# dsPIC_I2C.net
KiCad netlist of a schematic drawn in EAGLE
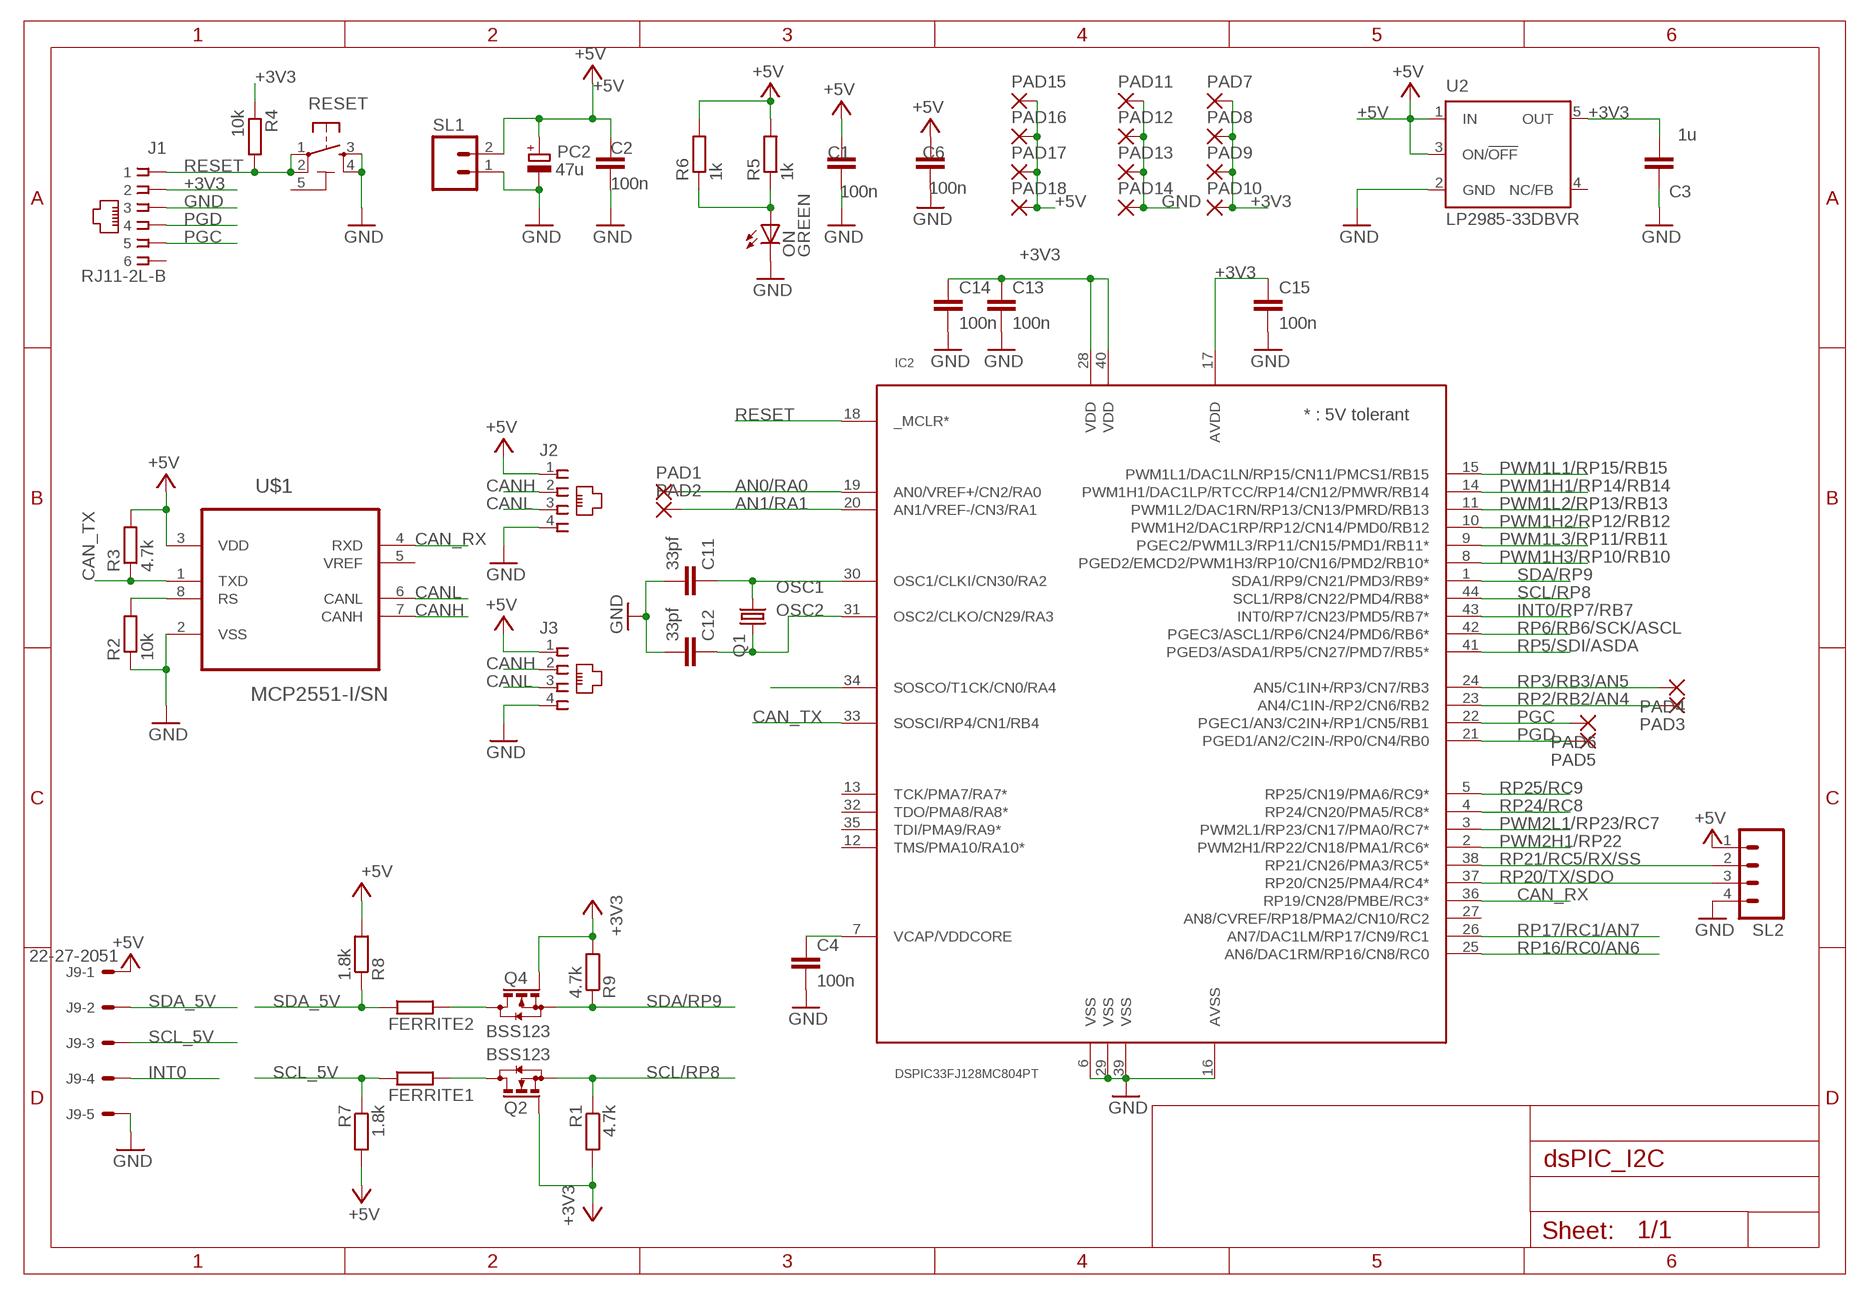
[diagram p0: schematic, sheet 1]

(export (version "E")
  (design (tool "Eeschema 10.0.6"))
  (components
    (comp (ref "C1")
      (value "100n")
      (footprint "eagle-import:C0603-ROUND")
      (libsource (lib "eagle-import") (part "C-EU0603-RND"))
    )
    (comp (ref "C2")
      (value "100n")
      (footprint "eagle-import:C0603-ROUND")
      (libsource (lib "eagle-import") (part "C-EU0603-RND"))
    )
    (comp (ref "C3")
      (value "1u")
      (footprint "eagle-import:C0603-ROUND")
      (libsource (lib "eagle-import") (part "C-EU0603-RND"))
    )
    (comp (ref "C4")
      (value "100n")
      (footprint "eagle-import:C0603K")
      (libsource (lib "eagle-import") (part "SmartPrj_C-EUC0603K"))
    )
    (comp (ref "C6")
      (value "100n")
      (footprint "eagle-import:C0603K")
      (libsource (lib "eagle-import") (part "SmartPrj_C-EUC0603K"))
    )
    (comp (ref "C11")
      (value "33pf")
      (footprint "eagle-import:C0603")
      (libsource (lib "eagle-import") (part "C-EUC0603"))
    )
    (comp (ref "C12")
      (value "33pf")
      (footprint "eagle-import:C0603")
      (libsource (lib "eagle-import") (part "C-EUC0603"))
    )
    (comp (ref "C13")
      (value "100n")
      (footprint "eagle-import:C0603")
      (libsource (lib "eagle-import") (part "C-EUC0603"))
    )
    (comp (ref "C14")
      (value "100n")
      (footprint "eagle-import:C0603")
      (libsource (lib "eagle-import") (part "C-EUC0603"))
    )
    (comp (ref "C15")
      (value "100n")
      (footprint "eagle-import:C0603")
      (libsource (lib "eagle-import") (part "C-EUC0603"))
    )
    (comp (ref "FERRITE1")
      (value "R-EU_M0805")
      (footprint "eagle-import:M0805")
      (libsource (lib "eagle-import") (part "R-EU_M0805"))
    )
    (comp (ref "FERRITE2")
      (value "R-EU_M0805")
      (footprint "eagle-import:M0805")
      (libsource (lib "eagle-import") (part "R-EU_M0805"))
    )
    (comp (ref "IC2")
      (value "DSPIC33FJ128MC804PT")
      (footprint "eagle-import:TQFP44")
      (libsource (lib "eagle-import") (part "DSPIC33F04PTJ128MC8"))
    )
    (comp (ref "J1")
      (value "RJ11-2L-B")
      (footprint "eagle-import:RJ11-NO_SHIELD")
      (fields (field (name "MF") "TYCO ELECTRONICS") (field (name "OC_FARNELL") "1393306"))
      (libsource (lib "eagle-import") (part "RJ11-2L-B"))
    )
    (comp (ref "J2")
      (value "520249-2")
      (footprint "eagle-import:520249-2")
      (libsource (lib "eagle-import") (part "520249-2"))
    )
    (comp (ref "J3")
      (value "520249-2")
      (footprint "eagle-import:520249-2")
      (libsource (lib "eagle-import") (part "520249-2"))
    )
    (comp (ref "J9")
      (value "22-27-2051")
      (footprint "eagle-import:6410-05")
      (libsource (lib "eagle-import") (part "22-?-0527-2051"))
    )
    (comp (ref "ON")
      (value "GREEN")
      (footprint "eagle-import:CHIP-LED0805")
      (libsource (lib "eagle-import") (part "LEDCHIP-LED0805"))
    )
    (comp (ref "PAD1")
      (value "1,6/0,9")
      (footprint "eagle-import:1,6_0,9")
      (libsource (lib "eagle-import") (part "1,6/0,9"))
    )
    (comp (ref "PAD2")
      (value "1,6/0,9")
      (footprint "eagle-import:1,6_0,9")
      (libsource (lib "eagle-import") (part "1,6/0,9"))
    )
    (comp (ref "PAD3")
      (value "1,6/0,9")
      (footprint "eagle-import:1,6_0,9")
      (libsource (lib "eagle-import") (part "1,6/0,9"))
    )
    (comp (ref "PAD4")
      (value "1,6/0,9")
      (footprint "eagle-import:1,6_0,9")
      (libsource (lib "eagle-import") (part "1,6/0,9"))
    )
    (comp (ref "PAD5")
      (value "1,6/0,9")
      (footprint "eagle-import:1,6_0,9")
      (libsource (lib "eagle-import") (part "1,6/0,9"))
    )
    (comp (ref "PAD6")
      (value "1,6/0,9")
      (footprint "eagle-import:1,6_0,9")
      (libsource (lib "eagle-import") (part "1,6/0,9"))
    )
    (comp (ref "PAD7")
      (value "1,6/0,9")
      (footprint "eagle-import:1,6_0,9")
      (libsource (lib "eagle-import") (part "1,6/0,9"))
    )
    (comp (ref "PAD8")
      (value "1,6/0,9")
      (footprint "eagle-import:1,6_0,9")
      (libsource (lib "eagle-import") (part "1,6/0,9"))
    )
    (comp (ref "PAD9")
      (value "1,6/0,9")
      (footprint "eagle-import:1,6_0,9")
      (libsource (lib "eagle-import") (part "1,6/0,9"))
    )
    (comp (ref "PAD10")
      (value "1,6/0,9")
      (footprint "eagle-import:1,6_0,9")
      (libsource (lib "eagle-import") (part "1,6/0,9"))
    )
    (comp (ref "PAD11")
      (value "1,6/0,9")
      (footprint "eagle-import:1,6_0,9")
      (libsource (lib "eagle-import") (part "1,6/0,9"))
    )
    (comp (ref "PAD12")
      (value "1,6/0,9")
      (footprint "eagle-import:1,6_0,9")
      (libsource (lib "eagle-import") (part "1,6/0,9"))
    )
    (comp (ref "PAD13")
      (value "1,6/0,9")
      (footprint "eagle-import:1,6_0,9")
      (libsource (lib "eagle-import") (part "1,6/0,9"))
    )
    (comp (ref "PAD14")
      (value "1,6/0,9")
      (footprint "eagle-import:1,6_0,9")
      (libsource (lib "eagle-import") (part "1,6/0,9"))
    )
    (comp (ref "PAD15")
      (value "1,6/0,9")
      (footprint "eagle-import:1,6_0,9")
      (libsource (lib "eagle-import") (part "1,6/0,9"))
    )
    (comp (ref "PAD16")
      (value "1,6/0,9")
      (footprint "eagle-import:1,6_0,9")
      (libsource (lib "eagle-import") (part "1,6/0,9"))
    )
    (comp (ref "PAD17")
      (value "1,6/0,9")
      (footprint "eagle-import:1,6_0,9")
      (libsource (lib "eagle-import") (part "1,6/0,9"))
    )
    (comp (ref "PAD18")
      (value "1,6/0,9")
      (footprint "eagle-import:1,6_0,9")
      (libsource (lib "eagle-import") (part "1,6/0,9"))
    )
    (comp (ref "PC2")
      (value "47u")
      (footprint "eagle-import:PANASONIC_D")
      (libsource (lib "eagle-import") (part "CPOL-EUD"))
    )
    (comp (ref "Q1")
      (value "CRYSTALSM49")
      (footprint "eagle-import:SM49")
      (fields (field (name "OC_FARNELL") "1842332"))
      (libsource (lib "eagle-import") (part "CRYSTALSM49"))
    )
    (comp (ref "Q2")
      (value "BSS123")
      (footprint "eagle-import:SOT23")
      (libsource (lib "eagle-import") (part "BSS123"))
    )
    (comp (ref "Q4")
      (value "BSS123")
      (footprint "eagle-import:SOT23")
      (libsource (lib "eagle-import") (part "BSS123"))
    )
    (comp (ref "R1")
      (value "4.7k")
      (footprint "eagle-import:R0805")
      (libsource (lib "eagle-import") (part "rcl_R-EU_R0805"))
    )
    (comp (ref "R2")
      (value "10k")
      (footprint "eagle-import:R0805")
      (libsource (lib "eagle-import") (part "R-EU_R0805"))
    )
    (comp (ref "R3")
      (value "4.7k")
      (footprint "eagle-import:R0805")
      (libsource (lib "eagle-import") (part "R-EU_R0805"))
    )
    (comp (ref "R4")
      (value "10k")
      (footprint "eagle-import:R0805")
      (libsource (lib "eagle-import") (part "R-EU_R0805"))
    )
    (comp (ref "R5")
      (value "1k")
      (footprint "eagle-import:R0805")
      (libsource (lib "eagle-import") (part "R-EU_R0805"))
    )
    (comp (ref "R6")
      (value "1k")
      (footprint "eagle-import:R0805")
      (libsource (lib "eagle-import") (part "R-EU_R0805"))
    )
    (comp (ref "R7")
      (value "1.8k")
      (footprint "eagle-import:0204_7")
      (libsource (lib "eagle-import") (part "rcl_R-EU_0204/7"))
    )
    (comp (ref "R8")
      (value "1.8k")
      (footprint "eagle-import:0204_7")
      (libsource (lib "eagle-import") (part "rcl_R-EU_0204/7"))
    )
    (comp (ref "R9")
      (value "4.7k")
      (footprint "eagle-import:R0805")
      (libsource (lib "eagle-import") (part "rcl_R-EU_R0805"))
    )
    (comp (ref "RESET")
      (value "TS42031-160R-TR-7260")
      (footprint "eagle-import:TS42")
      (libsource (lib "eagle-import") (part "TS42"))
    )
    (comp (ref "SL1")
      (value "M02")
      (footprint "eagle-import:02P")
      (libsource (lib "eagle-import") (part "M02"))
    )
    (comp (ref "SL2")
      (value "M04")
      (footprint "eagle-import:04P")
      (libsource (lib "eagle-import") (part "M04"))
    )
    (comp (ref "U$1")
      (value "MCP2551-I/SN")
      (footprint "eagle-import:SOIC127P600X175-8N")
      (libsource (lib "eagle-import") (part "MCP2551-I/SN"))
    )
    (comp (ref "U2")
      (value "LP2985-33DBVR")
      (footprint "eagle-import:SOT23-DBV")
      (libsource (lib "eagle-import") (part "LP2985-XXDBVR33"))
    )
  )
  (nets
    (net (code "1") (name "+3V3") (class "Default")
      (node (ref "C13") (pin "1") (pinfunction "1_1") (pintype "passive"))
      (node (ref "C14") (pin "1") (pinfunction "1_1") (pintype "passive"))
      (node (ref "C15") (pin "1") (pinfunction "1_1") (pintype "passive"))
      (node (ref "C3") (pin "2") (pinfunction "2_2") (pintype "passive"))
      (node (ref "IC2") (pin "17") (pinfunction "AVDD_17") (pintype "power_in"))
      (node (ref "IC2") (pin "28") (pinfunction "VDD_28") (pintype "power_in"))
      (node (ref "IC2") (pin "40") (pinfunction "VDD_40") (pintype "power_in"))
      (node (ref "J1") (pin "2") (pinfunction "2_2") (pintype "passive"))
      (node (ref "PAD10") (pin "1") (pinfunction "P_1") (pintype "passive"))
      (node (ref "PAD7") (pin "1") (pinfunction "P_1") (pintype "passive"))
      (node (ref "PAD8") (pin "1") (pinfunction "P_1") (pintype "passive"))
      (node (ref "PAD9") (pin "1") (pinfunction "P_1") (pintype "passive"))
      (node (ref "Q2") (pin "1") (pinfunction "G_1") (pintype "passive"))
      (node (ref "Q4") (pin "1") (pinfunction "G_1") (pintype "passive"))
      (node (ref "R1") (pin "2") (pinfunction "2_2") (pintype "passive"))
      (node (ref "R4") (pin "1") (pinfunction "1_1") (pintype "passive"))
      (node (ref "R9") (pin "2") (pinfunction "2_2") (pintype "passive"))
      (node (ref "U2") (pin "5") (pinfunction "OUT_5") (pintype "passive"))
    )
    (net (code "2") (name "+5V") (class "Default")
      (node (ref "C1") (pin "2") (pinfunction "2_2") (pintype "passive"))
      (node (ref "C2") (pin "2") (pinfunction "2_2") (pintype "passive"))
      (node (ref "C6") (pin "2") (pinfunction "2_2") (pintype "passive"))
      (node (ref "J2") (pin "1") (pinfunction "1_1") (pintype "passive"))
      (node (ref "J3") (pin "1") (pinfunction "1_1") (pintype "passive"))
      (node (ref "J9") (pin "1") (pinfunction "S_1") (pintype "passive"))
      (node (ref "PAD15") (pin "1") (pinfunction "P_1") (pintype "passive"))
      (node (ref "PAD16") (pin "1") (pinfunction "P_1") (pintype "passive"))
      (node (ref "PAD17") (pin "1") (pinfunction "P_1") (pintype "passive"))
      (node (ref "PAD18") (pin "1") (pinfunction "P_1") (pintype "passive"))
      (node (ref "PC2") (pin "+") (pinfunction "+_+") (pintype "passive"))
      (node (ref "R3") (pin "2") (pinfunction "2_2") (pintype "passive"))
      (node (ref "R5") (pin "2") (pinfunction "2_2") (pintype "passive"))
      (node (ref "R6") (pin "2") (pinfunction "2_2") (pintype "passive"))
      (node (ref "R7") (pin "2") (pinfunction "2_2") (pintype "passive"))
      (node (ref "R8") (pin "2") (pinfunction "2_2") (pintype "passive"))
      (node (ref "SL1") (pin "2") (pinfunction "2_2") (pintype "passive"))
      (node (ref "SL2") (pin "1") (pinfunction "1_1") (pintype "passive"))
      (node (ref "U$1") (pin "3") (pinfunction "VDD_3") (pintype "power_in"))
      (node (ref "U2") (pin "1") (pinfunction "IN_1") (pintype "input"))
      (node (ref "U2") (pin "3") (pinfunction "ON/~{OFF}_3") (pintype "input"))
    )
    (net (code "3") (name "/5-GND") (class "Default")
      (node (ref "RESET") (pin "5") (pinfunction "5-GND_5") (pintype "power_in"))
    )
    (net (code "4") (name "/AN0{slash}RA0") (class "Default")
      (node (ref "IC2") (pin "19") (pinfunction "AN0/VREF+/CN2/RA0_19") (pintype "bidirectional"))
      (node (ref "PAD1") (pin "1") (pinfunction "P_1") (pintype "passive"))
    )
    (net (code "5") (name "/AN1{slash}RA1") (class "Default")
      (node (ref "IC2") (pin "20") (pinfunction "AN1/VREF-/CN3/RA1_20") (pintype "bidirectional"))
      (node (ref "PAD2") (pin "1") (pinfunction "P_1") (pintype "passive"))
    )
    (net (code "6") (name "/CANH") (class "Default")
      (node (ref "J2") (pin "2") (pinfunction "2_2") (pintype "passive"))
      (node (ref "J3") (pin "2") (pinfunction "2_2") (pintype "passive"))
      (node (ref "U$1") (pin "7") (pinfunction "CANH_7") (pintype "bidirectional"))
    )
    (net (code "7") (name "/CANL") (class "Default")
      (node (ref "J2") (pin "3") (pinfunction "3_3") (pintype "passive"))
      (node (ref "J3") (pin "3") (pinfunction "3_3") (pintype "passive"))
      (node (ref "U$1") (pin "6") (pinfunction "CANL_6") (pintype "bidirectional"))
    )
    (net (code "8") (name "/CAN_RX") (class "Default")
      (node (ref "IC2") (pin "36") (pinfunction "RP19/CN28/PMBE/RC3*_36") (pintype "bidirectional"))
      (node (ref "U$1") (pin "4") (pinfunction "RXD_4") (pintype "output"))
    )
    (net (code "9") (name "/CAN_TX") (class "Default")
      (node (ref "IC2") (pin "33") (pinfunction "SOSCI/RP4/CN1/RB4_33") (pintype "bidirectional"))
      (node (ref "R3") (pin "1") (pinfunction "1_1") (pintype "passive"))
      (node (ref "U$1") (pin "1") (pinfunction "TXD_1") (pintype "input"))
    )
    (net (code "10") (name "/INT0") (class "Default")
      (node (ref "J9") (pin "4") (pinfunction "S_4") (pintype "passive"))
    )
    (net (code "11") (name "/INT0{slash}RP7{slash}RB7") (class "Default")
      (node (ref "IC2") (pin "43") (pinfunction "INT0/RP7/CN23/PMD5/RB7*_43") (pintype "bidirectional"))
    )
    (net (code "12") (name "/OSC1") (class "Default")
      (node (ref "C11") (pin "1") (pinfunction "1_1") (pintype "passive"))
      (node (ref "IC2") (pin "30") (pinfunction "OSC1/CLKI/CN30/RA2_30") (pintype "bidirectional"))
      (node (ref "Q1") (pin "1") (pinfunction "1_1") (pintype "passive"))
    )
    (net (code "13") (name "/OSC2") (class "Default")
      (node (ref "C12") (pin "1") (pinfunction "1_1") (pintype "passive"))
      (node (ref "IC2") (pin "31") (pinfunction "OSC2/CLKO/CN29/RA3_31") (pintype "bidirectional"))
      (node (ref "Q1") (pin "2") (pinfunction "2_2") (pintype "passive"))
    )
    (net (code "14") (name "/PGC") (class "Default")
      (node (ref "IC2") (pin "22") (pinfunction "PGEC1/AN3/C2IN+/RP1/CN5/RB1_22") (pintype "bidirectional"))
      (node (ref "J1") (pin "5") (pinfunction "5_5") (pintype "passive"))
      (node (ref "PAD6") (pin "1") (pinfunction "P_1") (pintype "passive"))
    )
    (net (code "15") (name "/PGD") (class "Default")
      (node (ref "IC2") (pin "21") (pinfunction "PGED1/AN2/C2IN-/RP0/CN4/RB0_21") (pintype "bidirectional"))
      (node (ref "J1") (pin "4") (pinfunction "4_4") (pintype "passive"))
      (node (ref "PAD5") (pin "1") (pinfunction "P_1") (pintype "passive"))
    )
    (net (code "16") (name "/PWM1H1{slash}RP14{slash}RB14") (class "Default")
      (node (ref "IC2") (pin "14") (pinfunction "PWM1H1/DAC1LP/RTCC/RP14/CN12/PMWR/RB14_14") (pintype "bidirectional"))
    )
    (net (code "17") (name "/PWM1H2{slash}RP12{slash}RB12") (class "Default")
      (node (ref "IC2") (pin "10") (pinfunction "PWM1H2/DAC1RP/RP12/CN14/PMD0/RB12_10") (pintype "bidirectional"))
    )
    (net (code "18") (name "/PWM1H3{slash}RP10{slash}RB10") (class "Default")
      (node (ref "IC2") (pin "8") (pinfunction "PGED2/EMCD2/PWM1H3/RP10/CN16/PMD2/RB10*_8") (pintype "bidirectional"))
    )
    (net (code "19") (name "/PWM1L1{slash}RP15{slash}RB15") (class "Default")
      (node (ref "IC2") (pin "15") (pinfunction "PWM1L1/DAC1LN/RP15/CN11/PMCS1/RB15_15") (pintype "bidirectional"))
    )
    (net (code "20") (name "/PWM1L2{slash}RP13{slash}RB13") (class "Default")
      (node (ref "IC2") (pin "11") (pinfunction "PWM1L2/DAC1RN/RP13/CN13/PMRD/RB13_11") (pintype "bidirectional"))
    )
    (net (code "21") (name "/PWM1L3{slash}RP11{slash}RB11") (class "Default")
      (node (ref "IC2") (pin "9") (pinfunction "PGEC2/PWM1L3/RP11/CN15/PMD1/RB11*_9") (pintype "bidirectional"))
    )
    (net (code "22") (name "/PWM2H1{slash}RP22") (class "Default")
      (node (ref "IC2") (pin "2") (pinfunction "PWM2H1/RP22/CN18/PMA1/RC6*_2") (pintype "bidirectional"))
    )
    (net (code "23") (name "/PWM2L1{slash}RP23{slash}RC7") (class "Default")
      (node (ref "IC2") (pin "3") (pinfunction "PWM2L1/RP23/CN17/PMA0/RC7*_3") (pintype "bidirectional"))
    )
    (net (code "24") (name "/RESET") (class "Default")
      (node (ref "IC2") (pin "18") (pinfunction "_MCLR*_18") (pintype "input"))
      (node (ref "J1") (pin "1") (pinfunction "1_1") (pintype "passive"))
      (node (ref "R4") (pin "2") (pinfunction "2_2") (pintype "passive"))
      (node (ref "RESET") (pin "1") (pinfunction "1_1") (pintype "passive"))
      (node (ref "RESET") (pin "2") (pinfunction "2_2") (pintype "passive"))
    )
    (net (code "25") (name "/RP2{slash}RB2{slash}AN4") (class "Default")
      (node (ref "IC2") (pin "23") (pinfunction "AN4/C1IN-/RP2/CN6/RB2_23") (pintype "bidirectional"))
      (node (ref "PAD3") (pin "1") (pinfunction "P_1") (pintype "passive"))
    )
    (net (code "26") (name "/RP3{slash}RB3{slash}AN5") (class "Default")
      (node (ref "IC2") (pin "24") (pinfunction "AN5/C1IN+/RP3/CN7/RB3_24") (pintype "bidirectional"))
      (node (ref "PAD4") (pin "1") (pinfunction "P_1") (pintype "passive"))
    )
    (net (code "27") (name "/RP5{slash}SDI{slash}ASDA") (class "Default")
      (node (ref "IC2") (pin "41") (pinfunction "PGED3/ASDA1/RP5/CN27/PMD7/RB5*_41") (pintype "bidirectional"))
    )
    (net (code "28") (name "/RP6{slash}RB6{slash}SCK{slash}ASCL") (class "Default")
      (node (ref "IC2") (pin "42") (pinfunction "PGEC3/ASCL1/RP6/CN24/PMD6/RB6*_42") (pintype "bidirectional"))
    )
    (net (code "29") (name "/RP16{slash}RC0{slash}AN6") (class "Default")
      (node (ref "IC2") (pin "25") (pinfunction "AN6/DAC1RM/RP16/CN8/RC0_25") (pintype "bidirectional"))
    )
    (net (code "30") (name "/RP17{slash}RC1{slash}AN7") (class "Default")
      (node (ref "IC2") (pin "26") (pinfunction "AN7/DAC1LM/RP17/CN9/RC1_26") (pintype "bidirectional"))
    )
    (net (code "31") (name "/RP20{slash}TX{slash}SDO") (class "Default")
      (node (ref "IC2") (pin "37") (pinfunction "RP20/CN25/PMA4/RC4*_37") (pintype "bidirectional"))
      (node (ref "SL2") (pin "3") (pinfunction "3_3") (pintype "passive"))
    )
    (net (code "32") (name "/RP21{slash}RC5{slash}RX{slash}SS") (class "Default")
      (node (ref "IC2") (pin "38") (pinfunction "RP21/CN26/PMA3/RC5*_38") (pintype "bidirectional"))
      (node (ref "SL2") (pin "2") (pinfunction "2_2") (pintype "passive"))
    )
    (net (code "33") (name "/RP24{slash}RC8") (class "Default")
      (node (ref "IC2") (pin "4") (pinfunction "RP24/CN20/PMA5/RC8*_4") (pintype "bidirectional"))
    )
    (net (code "34") (name "/RP25{slash}RC9") (class "Default")
      (node (ref "IC2") (pin "5") (pinfunction "RP25/CN19/PMA6/RC9*_5") (pintype "bidirectional"))
    )
    (net (code "35") (name "/SCL_5V") (class "Default")
      (node (ref "FERRITE1") (pin "1") (pinfunction "1_1") (pintype "passive"))
      (node (ref "J9") (pin "3") (pinfunction "S_3") (pintype "passive"))
      (node (ref "R7") (pin "1") (pinfunction "1_1") (pintype "passive"))
    )
    (net (code "36") (name "/SCL{slash}RP8") (class "Default")
      (node (ref "IC2") (pin "44") (pinfunction "SCL1/RP8/CN22/PMD4/RB8*_44") (pintype "bidirectional"))
      (node (ref "Q2") (pin "2") (pinfunction "S_2") (pintype "passive"))
      (node (ref "R1") (pin "1") (pinfunction "1_1") (pintype "passive"))
    )
    (net (code "37") (name "/SDA_5V") (class "Default")
      (node (ref "FERRITE2") (pin "1") (pinfunction "1_1") (pintype "passive"))
      (node (ref "J9") (pin "2") (pinfunction "S_2") (pintype "passive"))
      (node (ref "R8") (pin "1") (pinfunction "1_1") (pintype "passive"))
    )
    (net (code "38") (name "/SDA{slash}RP9") (class "Default")
      (node (ref "IC2") (pin "1") (pinfunction "SDA1/RP9/CN21/PMD3/RB9*_1") (pintype "bidirectional"))
      (node (ref "Q4") (pin "2") (pinfunction "S_2") (pintype "passive"))
      (node (ref "R9") (pin "1") (pinfunction "1_1") (pintype "passive"))
    )
    (net (code "39") (name "GND") (class "Default")
      (node (ref "C1") (pin "1") (pinfunction "1_1") (pintype "passive"))
      (node (ref "C11") (pin "2") (pinfunction "2_2") (pintype "passive"))
      (node (ref "C12") (pin "2") (pinfunction "2_2") (pintype "passive"))
      (node (ref "C13") (pin "2") (pinfunction "2_2") (pintype "passive"))
      (node (ref "C14") (pin "2") (pinfunction "2_2") (pintype "passive"))
      (node (ref "C15") (pin "2") (pinfunction "2_2") (pintype "passive"))
      (node (ref "C2") (pin "1") (pinfunction "1_1") (pintype "passive"))
      (node (ref "C3") (pin "1") (pinfunction "1_1") (pintype "passive"))
      (node (ref "C4") (pin "2") (pinfunction "2_2") (pintype "passive"))
      (node (ref "C6") (pin "1") (pinfunction "1_1") (pintype "passive"))
      (node (ref "IC2") (pin "16") (pinfunction "AVSS_16") (pintype "power_in"))
      (node (ref "IC2") (pin "29") (pinfunction "VSS_29") (pintype "power_in"))
      (node (ref "IC2") (pin "39") (pinfunction "VSS_39") (pintype "power_in"))
      (node (ref "IC2") (pin "6") (pinfunction "VSS_6") (pintype "power_in"))
      (node (ref "J1") (pin "3") (pinfunction "3_3") (pintype "passive"))
      (node (ref "J2") (pin "4") (pinfunction "4_4") (pintype "passive"))
      (node (ref "J3") (pin "4") (pinfunction "4_4") (pintype "passive"))
      (node (ref "J9") (pin "5") (pinfunction "S_5") (pintype "passive"))
      (node (ref "ON") (pin "C") (pinfunction "C_C") (pintype "passive"))
      (node (ref "PAD11") (pin "1") (pinfunction "P_1") (pintype "passive"))
      (node (ref "PAD12") (pin "1") (pinfunction "P_1") (pintype "passive"))
      (node (ref "PAD13") (pin "1") (pinfunction "P_1") (pintype "passive"))
      (node (ref "PAD14") (pin "1") (pinfunction "P_1") (pintype "passive"))
      (node (ref "PC2") (pin "-") (pinfunction "-_-") (pintype "passive"))
      (node (ref "R2") (pin "1") (pinfunction "1_1") (pintype "passive"))
      (node (ref "RESET") (pin "3") (pinfunction "3_3") (pintype "passive"))
      (node (ref "RESET") (pin "4") (pinfunction "4_4") (pintype "passive"))
      (node (ref "SL1") (pin "1") (pinfunction "1_1") (pintype "passive"))
      (node (ref "SL2") (pin "4") (pinfunction "4_4") (pintype "passive"))
      (node (ref "U$1") (pin "2") (pinfunction "VSS_2") (pintype "passive"))
      (node (ref "U2") (pin "2") (pinfunction "GND_2") (pintype "power_in"))
    )
    (net (code "40") (name "Net-(IC2-VCAP{slash}VDDCORE)") (class "Default")
      (node (ref "C4") (pin "1") (pinfunction "1_1") (pintype "passive"))
      (node (ref "IC2") (pin "7") (pinfunction "VCAP/VDDCORE_7") (pintype "power_in"))
    )
    (net (code "41") (name "Net-(ON-PadA)") (class "Default")
      (node (ref "ON") (pin "A") (pinfunction "A_A") (pintype "passive"))
      (node (ref "R5") (pin "1") (pinfunction "1_1") (pintype "passive"))
      (node (ref "R6") (pin "1") (pinfunction "1_1") (pintype "passive"))
    )
    (net (code "42") (name "Net-(Q2-D)") (class "Default")
      (node (ref "FERRITE1") (pin "2") (pinfunction "2_2") (pintype "passive"))
      (node (ref "Q2") (pin "3") (pinfunction "D_3") (pintype "passive"))
    )
    (net (code "43") (name "Net-(Q4-D)") (class "Default")
      (node (ref "FERRITE2") (pin "2") (pinfunction "2_2") (pintype "passive"))
      (node (ref "Q4") (pin "3") (pinfunction "D_3") (pintype "passive"))
    )
    (net (code "44") (name "Net-(U$1-RS)") (class "Default")
      (node (ref "R2") (pin "2") (pinfunction "2_2") (pintype "passive"))
      (node (ref "U$1") (pin "8") (pinfunction "RS_8") (pintype "input"))
    )
    (net (code "45") (name "unconnected-(IC2-AN8{slash}CVREF{slash}RP18{slash}PMA2{slash}CN10{slash}RC2-Pad27)") (class "Default")
      (node (ref "IC2") (pin "27") (pinfunction "AN8/CVREF/RP18/PMA2/CN10/RC2_27") (pintype "bidirectional"))
    )
    (net (code "46") (name "unconnected-(IC2-SOSCO{slash}T1CK{slash}CN0{slash}RA4-Pad34)") (class "Default")
      (node (ref "IC2") (pin "34") (pinfunction "SOSCO/T1CK/CN0/RA4_34") (pintype "bidirectional"))
    )
    (net (code "47") (name "unconnected-(IC2-TCK{slash}PMA7{slash}RA7*-Pad13)") (class "Default")
      (node (ref "IC2") (pin "13") (pinfunction "TCK/PMA7/RA7*_13") (pintype "bidirectional"))
    )
    (net (code "48") (name "unconnected-(IC2-TDI{slash}PMA9{slash}RA9*-Pad35)") (class "Default")
      (node (ref "IC2") (pin "35") (pinfunction "TDI/PMA9/RA9*_35") (pintype "bidirectional"))
    )
    (net (code "49") (name "unconnected-(IC2-TDO{slash}PMA8{slash}RA8*-Pad32)") (class "Default")
      (node (ref "IC2") (pin "32") (pinfunction "TDO/PMA8/RA8*_32") (pintype "bidirectional"))
    )
    (net (code "50") (name "unconnected-(IC2-TMS{slash}PMA10{slash}RA10*-Pad12)") (class "Default")
      (node (ref "IC2") (pin "12") (pinfunction "TMS/PMA10/RA10*_12") (pintype "bidirectional"))
    )
    (net (code "51") (name "unconnected-(J1-Pad6)") (class "Default")
      (node (ref "J1") (pin "6") (pinfunction "6_6") (pintype "passive"))
    )
    (net (code "52") (name "unconnected-(U$1-VREF-Pad5)") (class "Default")
      (node (ref "U$1") (pin "5") (pinfunction "VREF_5") (pintype "output"))
    )
    (net (code "53") (name "unconnected-(U2-NC{slash}FB-Pad4)") (class "Default")
      (node (ref "U2") (pin "4") (pinfunction "NC/FB_4") (pintype "passive"))
    )
  )
)
